# Sheet1.net
KiCad netlist of a schematic drawn in Altium Designer
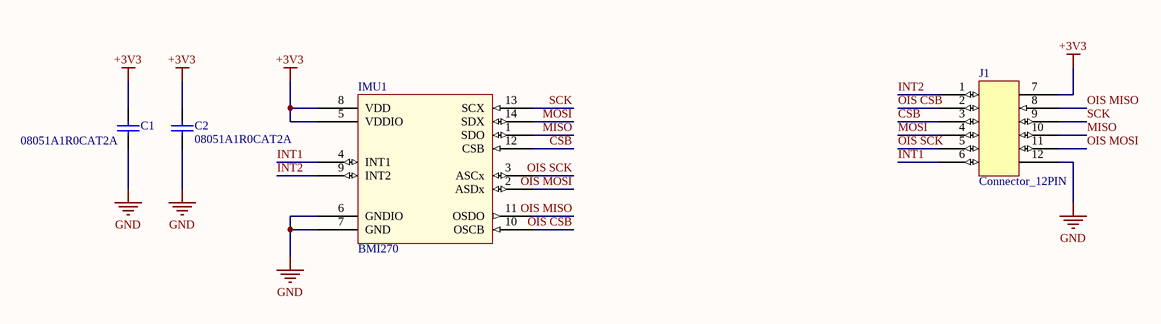
[diagram p0: Sheet1.SchDoc]

(export (version "E")
  (design (tool "Eeschema 10.0.6"))
  (components
    (comp (ref "C1")
      (value "08051A1R0CAT2A")
      (footprint "CAPC2013X140X50ML20T25")
      (fields (field (name "MANUFACTURER") "AVX Interconnect / Elco"))
      (libsource (lib "Altium Content Vault") (part "CAP"))
    )
    (comp (ref "C2")
      (value "08051A1R0CAT2A")
      (footprint "CAPC2013X140X50ML20T25")
      (fields (field (name "MANUFACTURER") "AVX Interconnect / Elco"))
      (libsource (lib "Altium Content Vault") (part "CAP"))
    )
    (comp (ref "IMU1")
      (value "BMI270")
      (footprint "LGA14_3x2.5x0.8mm")
      (libsource (lib "moma_altium_library") (part "BMI270"))
    )
    (comp (ref "J1")
      (value "Connector_12PIN")
      (footprint "12PIN_connector")
      (libsource (lib "moma_altium_library") (part "Connector_12PIN"))
    )
  )
  (nets
    (net (code "1") (name "+3V3") (class "Default")
      (node (ref "C1") (pin "2") (pinfunction "2_2") (pintype "passive"))
      (node (ref "C2") (pin "2") (pinfunction "2_2") (pintype "passive"))
      (node (ref "IMU1") (pin "5") (pinfunction "VDDIO_5") (pintype "power_in"))
      (node (ref "IMU1") (pin "8") (pinfunction "VDD_8") (pintype "power_in"))
      (node (ref "J1") (pin "7") (pintype "power_in"))
    )
    (net (code "2") (name "/CSB") (class "Default")
      (node (ref "IMU1") (pin "12") (pinfunction "CSB_12") (pintype "input"))
      (node (ref "J1") (pin "3") (pintype "bidirectional"))
    )
    (net (code "3") (name "/INT1") (class "Default")
      (node (ref "IMU1") (pin "4") (pinfunction "INT1_4") (pintype "bidirectional"))
      (node (ref "J1") (pin "6") (pintype "bidirectional"))
    )
    (net (code "4") (name "/INT2") (class "Default")
      (node (ref "IMU1") (pin "9") (pinfunction "INT2_9") (pintype "bidirectional"))
      (node (ref "J1") (pin "1") (pintype "bidirectional"))
    )
    (net (code "5") (name "/MISO") (class "Default")
      (node (ref "IMU1") (pin "1") (pinfunction "SDO_1") (pintype "bidirectional"))
      (node (ref "J1") (pin "10") (pintype "bidirectional"))
    )
    (net (code "6") (name "/MOSI") (class "Default")
      (node (ref "IMU1") (pin "14") (pinfunction "SDX_14") (pintype "bidirectional"))
      (node (ref "J1") (pin "4") (pintype "bidirectional"))
    )
    (net (code "7") (name "/OIS CSB") (class "Default")
      (node (ref "IMU1") (pin "10") (pinfunction "OSCB_10") (pintype "input"))
      (node (ref "J1") (pin "2") (pintype "bidirectional"))
    )
    (net (code "8") (name "/OIS MISO") (class "Default")
      (node (ref "IMU1") (pin "11") (pinfunction "OSDO_11") (pintype "output"))
      (node (ref "J1") (pin "8") (pintype "input"))
    )
    (net (code "9") (name "/OIS MOSI") (class "Default")
      (node (ref "IMU1") (pin "2") (pinfunction "ASDx_2") (pintype "bidirectional"))
      (node (ref "J1") (pin "11") (pintype "bidirectional"))
    )
    (net (code "10") (name "/OIS SCK") (class "Default")
      (node (ref "IMU1") (pin "3") (pinfunction "ASCx_3") (pintype "bidirectional"))
      (node (ref "J1") (pin "5") (pintype "bidirectional"))
    )
    (net (code "11") (name "/SCK") (class "Default")
      (node (ref "IMU1") (pin "13") (pinfunction "SCX_13") (pintype "input"))
      (node (ref "J1") (pin "9") (pintype "bidirectional"))
    )
    (net (code "12") (name "GND") (class "Default")
      (node (ref "C1") (pin "1") (pinfunction "1_1") (pintype "passive"))
      (node (ref "C2") (pin "1") (pinfunction "1_1") (pintype "passive"))
      (node (ref "IMU1") (pin "6") (pinfunction "GNDIO_6") (pintype "power_in"))
      (node (ref "IMU1") (pin "7") (pinfunction "GND_7") (pintype "power_in"))
      (node (ref "J1") (pin "12") (pintype "power_in"))
    )
  )
)
